# displayBoard.net
KiCad netlist of a schematic drawn in EAGLE
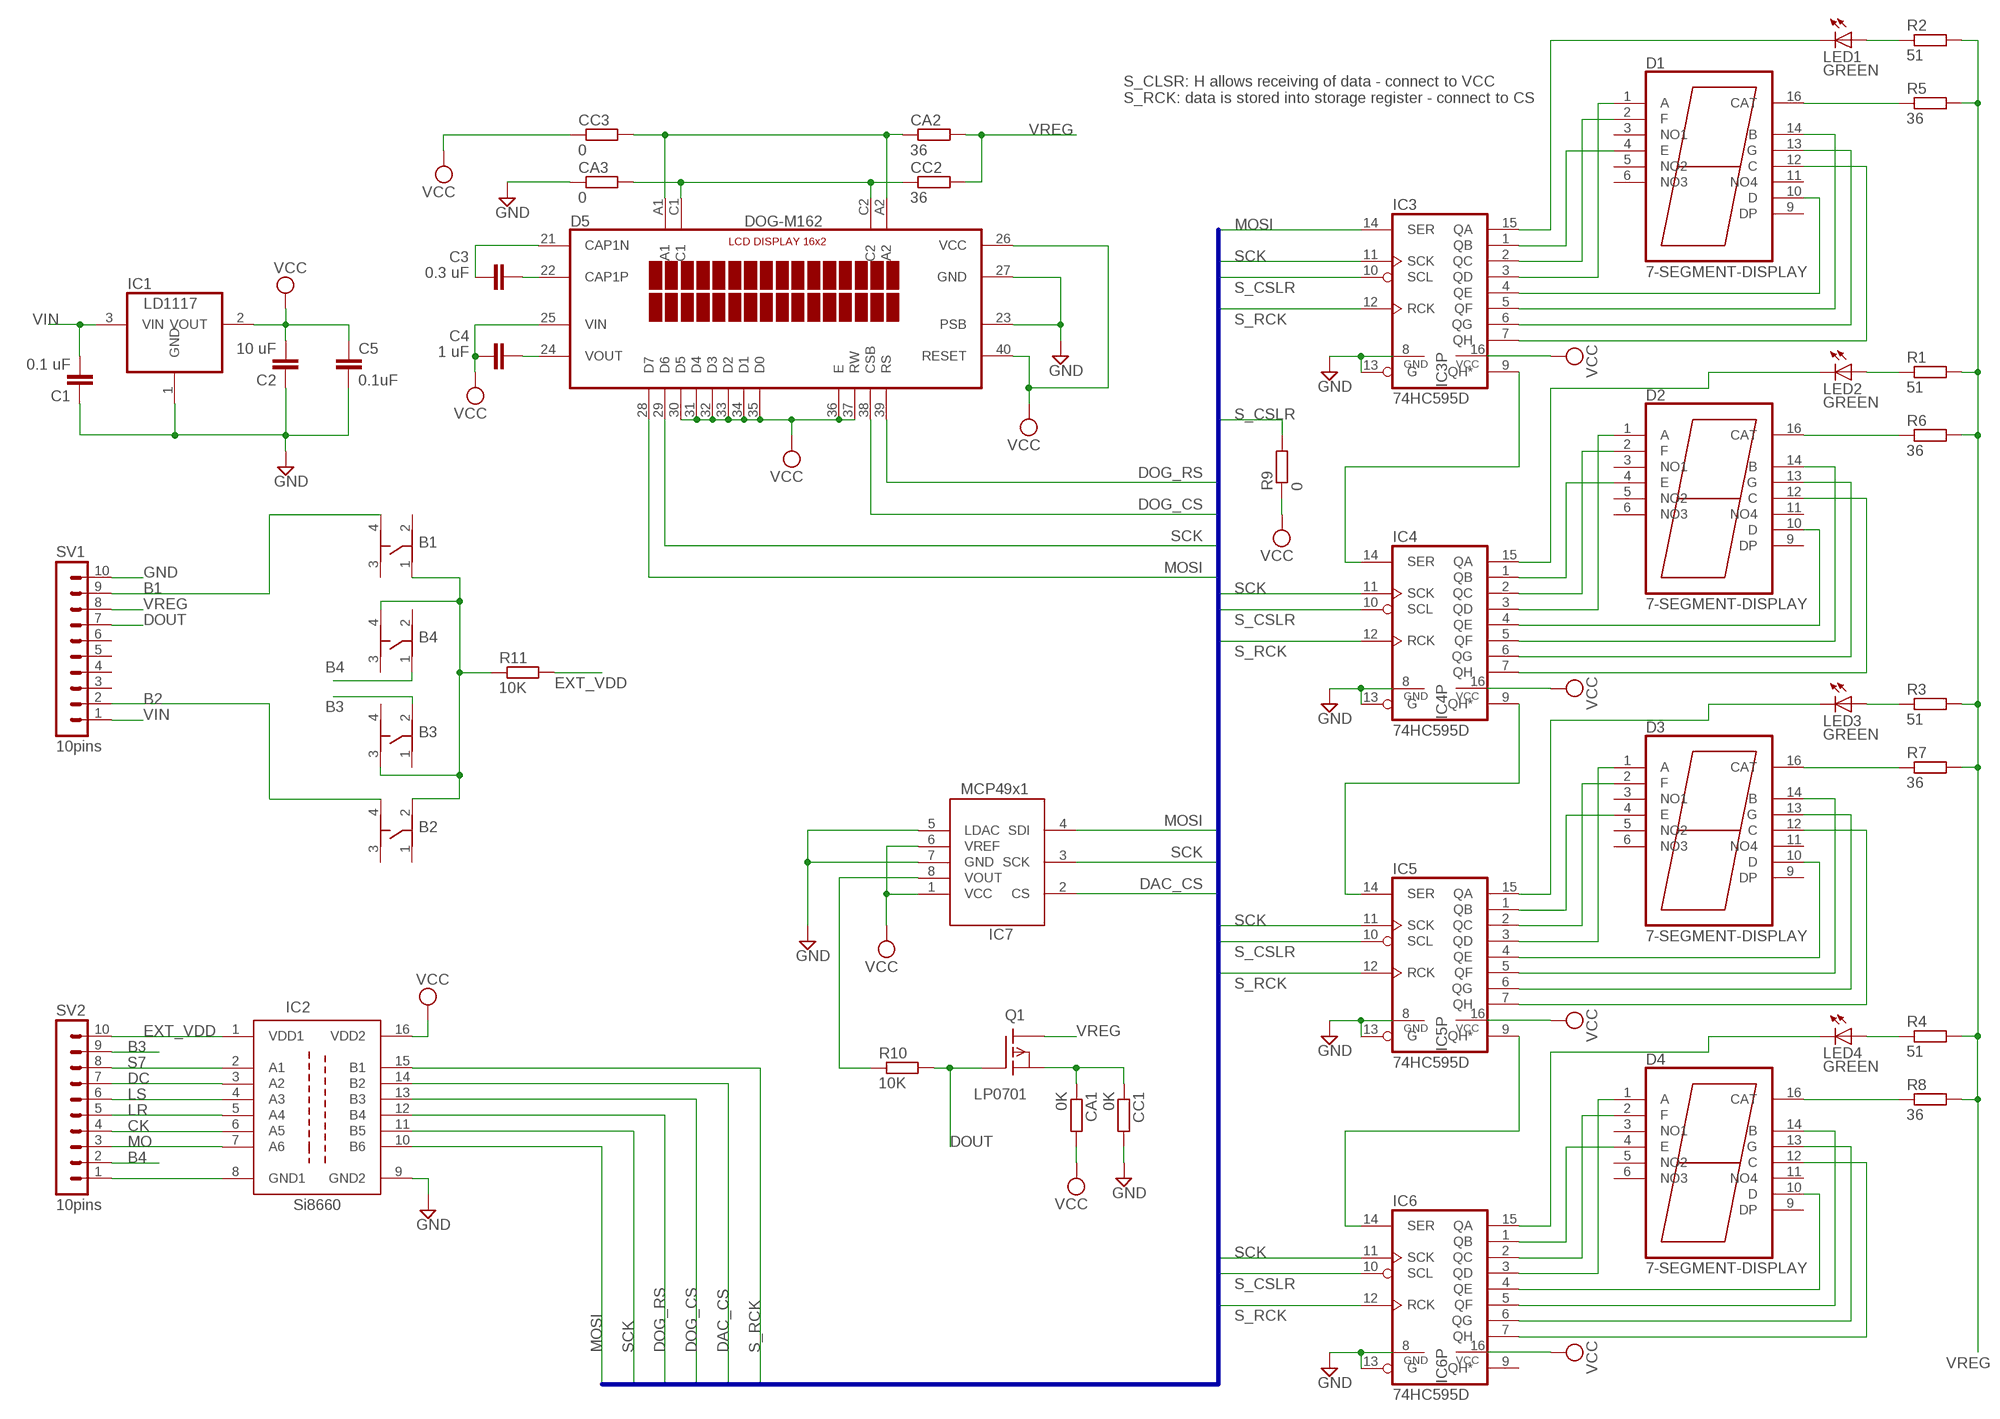
[diagram p0: schematic, sheet 1]

(export (version "E")
  (design (tool "Eeschema 10.0.6"))
  (components
    (comp (ref "B1")
      (value "BUTTON-D6X")
      (footprint "eagle-import:BUTTON-D6X")
      (libsource (lib "eagle-import") (part "BUTTON-D6X"))
    )
    (comp (ref "B2")
      (value "BUTTON-D6X")
      (footprint "eagle-import:BUTTON-D6X")
      (libsource (lib "eagle-import") (part "BUTTON-D6X"))
    )
    (comp (ref "B3")
      (value "BUTTON-D6X")
      (footprint "eagle-import:BUTTON-D6X")
      (libsource (lib "eagle-import") (part "BUTTON-D6X"))
    )
    (comp (ref "B4")
      (value "BUTTON-D6X")
      (footprint "eagle-import:BUTTON-D6X")
      (libsource (lib "eagle-import") (part "BUTTON-D6X"))
    )
    (comp (ref "C1")
      (value "0.1 uF")
      (footprint "eagle-import:C1206")
      (libsource (lib "eagle-import") (part "C-EUC1206"))
    )
    (comp (ref "C2")
      (value "10 uF")
      (footprint "eagle-import:C1206")
      (libsource (lib "eagle-import") (part "C-EUC1206"))
    )
    (comp (ref "C3")
      (value "0.3 uF")
      (footprint "eagle-import:C1206")
      (libsource (lib "eagle-import") (part "C-EUC1206"))
    )
    (comp (ref "C4")
      (value "1 uF")
      (footprint "eagle-import:C1206")
      (libsource (lib "eagle-import") (part "C-EUC1206"))
    )
    (comp (ref "C5")
      (value "0.1uF")
      (footprint "eagle-import:C1206")
      (libsource (lib "eagle-import") (part "C-EUC1206"))
    )
    (comp (ref "CA1")
      (value "0K")
      (footprint "eagle-import:R1206")
      (libsource (lib "eagle-import") (part "R-EU_R1206"))
    )
    (comp (ref "CA2")
      (value "36")
      (footprint "eagle-import:R1206")
      (libsource (lib "eagle-import") (part "R-EU_R1206"))
    )
    (comp (ref "CA3")
      (value "0")
      (footprint "eagle-import:R1206")
      (libsource (lib "eagle-import") (part "R-EU_R1206"))
    )
    (comp (ref "CC1")
      (value "0K")
      (footprint "eagle-import:R1206")
      (libsource (lib "eagle-import") (part "R-EU_R1206"))
    )
    (comp (ref "CC2")
      (value "36")
      (footprint "eagle-import:R1206")
      (libsource (lib "eagle-import") (part "R-EU_R1206"))
    )
    (comp (ref "CC3")
      (value "0")
      (footprint "eagle-import:R1206")
      (libsource (lib "eagle-import") (part "R-EU_R1206"))
    )
    (comp (ref "D1")
      (value "7-SEGMENT-DISPLAY")
      (footprint "eagle-import:LDS-A812")
      (libsource (lib "eagle-import") (part "7-SEGMENT-DISPLAY"))
    )
    (comp (ref "D2")
      (value "7-SEGMENT-DISPLAY")
      (footprint "eagle-import:LDS-A812")
      (libsource (lib "eagle-import") (part "7-SEGMENT-DISPLAY"))
    )
    (comp (ref "D3")
      (value "7-SEGMENT-DISPLAY")
      (footprint "eagle-import:LDS-A812")
      (libsource (lib "eagle-import") (part "7-SEGMENT-DISPLAY"))
    )
    (comp (ref "D4")
      (value "7-SEGMENT-DISPLAY")
      (footprint "eagle-import:LDS-A812")
      (libsource (lib "eagle-import") (part "7-SEGMENT-DISPLAY"))
    )
    (comp (ref "D5")
      (value "DOG-M162")
      (footprint "eagle-import:DOGM162")
      (libsource (lib "eagle-import") (part "DOG-M162"))
    )
    (comp (ref "IC1")
      (value "LD1117")
      (footprint "eagle-import:SOT223")
      (fields (field (name "MPN") "REG1117"))
      (libsource (lib "eagle-import") (part "REG1117"))
    )
    (comp (ref "IC2")
      (value "SI-8660")
      (footprint "eagle-import:SOP-16")
      (libsource (lib "eagle-import") (part "SI-8660"))
    )
    (comp (ref "IC3")
      (value "74HC595D")
      (footprint "eagle-import:SO16")
      (libsource (lib "eagle-import") (part "74595DHC"))
    )
    (comp (ref "IC4")
      (value "74HC595D")
      (footprint "eagle-import:SO16")
      (libsource (lib "eagle-import") (part "74595DHC"))
    )
    (comp (ref "IC5")
      (value "74HC595D")
      (footprint "eagle-import:SO16")
      (libsource (lib "eagle-import") (part "74595DHC"))
    )
    (comp (ref "IC6")
      (value "74HC595D")
      (footprint "eagle-import:SO16")
      (libsource (lib "eagle-import") (part "74595DHC"))
    )
    (comp (ref "IC7")
      (value "MCP4921")
      (footprint "eagle-import:MSOP-8")
      (libsource (lib "eagle-import") (part "MCP4901"))
    )
    (comp (ref "LED1")
      (value "GREEN")
      (footprint "eagle-import:LED3MM")
      (libsource (lib "eagle-import") (part "LED3MM"))
    )
    (comp (ref "LED2")
      (value "GREEN")
      (footprint "eagle-import:LED3MM")
      (libsource (lib "eagle-import") (part "LED3MM"))
    )
    (comp (ref "LED3")
      (value "GREEN")
      (footprint "eagle-import:LED3MM")
      (libsource (lib "eagle-import") (part "LED3MM"))
    )
    (comp (ref "LED4")
      (value "GREEN")
      (footprint "eagle-import:LED3MM")
      (libsource (lib "eagle-import") (part "LED3MM"))
    )
    (comp (ref "Q1")
      (value "LP0701")
      (footprint "eagle-import:TO-92")
      (libsource (lib "eagle-import") (part "LP0701N3"))
    )
    (comp (ref "R1")
      (value "51")
      (footprint "eagle-import:R1206")
      (libsource (lib "eagle-import") (part "R-EU_R1206"))
    )
    (comp (ref "R2")
      (value "51")
      (footprint "eagle-import:R1206")
      (libsource (lib "eagle-import") (part "R-EU_R1206"))
    )
    (comp (ref "R3")
      (value "51")
      (footprint "eagle-import:R1206")
      (libsource (lib "eagle-import") (part "R-EU_R1206"))
    )
    (comp (ref "R4")
      (value "51")
      (footprint "eagle-import:R1206")
      (libsource (lib "eagle-import") (part "R-EU_R1206"))
    )
    (comp (ref "R5")
      (value "36")
      (footprint "eagle-import:R1206")
      (libsource (lib "eagle-import") (part "R-EU_R1206"))
    )
    (comp (ref "R6")
      (value "36")
      (footprint "eagle-import:R1206")
      (libsource (lib "eagle-import") (part "R-EU_R1206"))
    )
    (comp (ref "R7")
      (value "36")
      (footprint "eagle-import:R1206")
      (libsource (lib "eagle-import") (part "R-EU_R1206"))
    )
    (comp (ref "R8")
      (value "36")
      (footprint "eagle-import:R1206")
      (libsource (lib "eagle-import") (part "R-EU_R1206"))
    )
    (comp (ref "R9")
      (value "0")
      (footprint "eagle-import:R1206")
      (libsource (lib "eagle-import") (part "R-EU_R1206"))
    )
    (comp (ref "R10")
      (value "10K")
      (footprint "eagle-import:R1206")
      (libsource (lib "eagle-import") (part "R-EU_R1206"))
    )
    (comp (ref "R11")
      (value "10K")
      (footprint "eagle-import:R1206")
      (libsource (lib "eagle-import") (part "R-EU_R1206"))
    )
    (comp (ref "SV1")
      (value "10pins")
      (footprint "eagle-import:MA10-1")
      (libsource (lib "eagle-import") (part "MA10-1"))
    )
    (comp (ref "SV2")
      (value "10pins")
      (footprint "eagle-import:MA10-1")
      (libsource (lib "eagle-import") (part "MA10-1"))
    )
  )
  (nets
    (net (code "1") (name "/B1") (class "Default")
      (node (ref "B1") (pin "4") (pinfunction "4_4") (pintype "bidirectional"))
      (node (ref "SV1") (pin "9") (pinfunction "9_9") (pintype "passive"))
    )
    (net (code "2") (name "/B2") (class "Default")
      (node (ref "B2") (pin "4") (pinfunction "4_4") (pintype "bidirectional"))
      (node (ref "SV1") (pin "2") (pinfunction "2_2") (pintype "passive"))
    )
    (net (code "3") (name "/B3") (class "Default")
      (node (ref "B3") (pin "2") (pinfunction "2_2") (pintype "bidirectional"))
      (node (ref "SV2") (pin "9") (pinfunction "9_9") (pintype "passive"))
    )
    (net (code "4") (name "/B4") (class "Default")
      (node (ref "B4") (pin "1") (pinfunction "1_1") (pintype "bidirectional"))
      (node (ref "SV2") (pin "2") (pinfunction "2_2") (pintype "passive"))
    )
    (net (code "5") (name "/CK") (class "Default")
      (node (ref "IC2") (pin "6") (pinfunction "A5_6") (pintype "bidirectional"))
      (node (ref "SV2") (pin "4") (pinfunction "4_4") (pintype "passive"))
    )
    (net (code "6") (name "/DAC_CS") (class "Default")
      (node (ref "IC2") (pin "14") (pinfunction "B2_14") (pintype "bidirectional"))
      (node (ref "IC7") (pin "2") (pinfunction "CS_2") (pintype "bidirectional"))
    )
    (net (code "7") (name "/DC") (class "Default")
      (node (ref "IC2") (pin "3") (pinfunction "A2_3") (pintype "bidirectional"))
      (node (ref "SV2") (pin "7") (pinfunction "7_7") (pintype "passive"))
    )
    (net (code "8") (name "/DOG_CS") (class "Default")
      (node (ref "D5") (pin "38") (pinfunction "CSB_38") (pintype "bidirectional"))
      (node (ref "IC2") (pin "13") (pinfunction "B3_13") (pintype "bidirectional"))
    )
    (net (code "9") (name "/DOG_RS") (class "Default")
      (node (ref "D5") (pin "39") (pinfunction "RS_39") (pintype "bidirectional"))
      (node (ref "IC2") (pin "12") (pinfunction "B4_12") (pintype "bidirectional"))
    )
    (net (code "10") (name "/DOUT") (class "Default")
      (node (ref "Q1") (pin "2") (pinfunction "G_2") (pintype "passive"))
      (node (ref "R10") (pin "2") (pinfunction "2_2") (pintype "passive"))
      (node (ref "SV1") (pin "7") (pinfunction "7_7") (pintype "passive"))
    )
    (net (code "11") (name "/EXT_VDD") (class "Default")
      (node (ref "IC2") (pin "1") (pinfunction "VDD1_1") (pintype "bidirectional"))
      (node (ref "R11") (pin "2") (pinfunction "2_2") (pintype "passive"))
      (node (ref "SV2") (pin "10") (pinfunction "10_10") (pintype "passive"))
    )
    (net (code "12") (name "/LR") (class "Default")
      (node (ref "IC2") (pin "5") (pinfunction "A4_5") (pintype "bidirectional"))
      (node (ref "SV2") (pin "5") (pinfunction "5_5") (pintype "passive"))
    )
    (net (code "13") (name "/LS") (class "Default")
      (node (ref "IC2") (pin "4") (pinfunction "A3_4") (pintype "bidirectional"))
      (node (ref "SV2") (pin "6") (pinfunction "6_6") (pintype "passive"))
    )
    (net (code "14") (name "/MO") (class "Default")
      (node (ref "IC2") (pin "7") (pinfunction "A6_7") (pintype "bidirectional"))
      (node (ref "SV2") (pin "3") (pinfunction "3_3") (pintype "passive"))
    )
    (net (code "15") (name "/MOSI") (class "Default")
      (node (ref "D5") (pin "28") (pinfunction "D7_28") (pintype "bidirectional"))
      (node (ref "IC2") (pin "10") (pinfunction "B6_10") (pintype "bidirectional"))
      (node (ref "IC3") (pin "14") (pinfunction "SER_14") (pintype "input"))
      (node (ref "IC7") (pin "4") (pinfunction "SDI_4") (pintype "bidirectional"))
    )
    (net (code "16") (name "/S7") (class "Default")
      (node (ref "IC2") (pin "2") (pinfunction "A1_2") (pintype "bidirectional"))
      (node (ref "SV2") (pin "8") (pinfunction "8_8") (pintype "passive"))
    )
    (net (code "17") (name "/SCK") (class "Default")
      (node (ref "D5") (pin "29") (pinfunction "D6_29") (pintype "bidirectional"))
      (node (ref "IC2") (pin "11") (pinfunction "B5_11") (pintype "bidirectional"))
      (node (ref "IC3") (pin "11") (pinfunction "SCK_11") (pintype "input"))
      (node (ref "IC4") (pin "11") (pinfunction "SCK_11") (pintype "input"))
      (node (ref "IC5") (pin "11") (pinfunction "SCK_11") (pintype "input"))
      (node (ref "IC6") (pin "11") (pinfunction "SCK_11") (pintype "input"))
      (node (ref "IC7") (pin "3") (pinfunction "SCK_3") (pintype "bidirectional"))
    )
    (net (code "18") (name "/S_CSLR") (class "Default")
      (node (ref "IC3") (pin "10") (pinfunction "SCL_10") (pintype "input"))
      (node (ref "IC4") (pin "10") (pinfunction "SCL_10") (pintype "input"))
      (node (ref "IC5") (pin "10") (pinfunction "SCL_10") (pintype "input"))
      (node (ref "IC6") (pin "10") (pinfunction "SCL_10") (pintype "input"))
      (node (ref "R9") (pin "2") (pinfunction "2_2") (pintype "passive"))
    )
    (net (code "19") (name "/S_RCK") (class "Default")
      (node (ref "IC2") (pin "15") (pinfunction "B1_15") (pintype "bidirectional"))
      (node (ref "IC3") (pin "12") (pinfunction "RCK_12") (pintype "input"))
      (node (ref "IC4") (pin "12") (pinfunction "RCK_12") (pintype "input"))
      (node (ref "IC5") (pin "12") (pinfunction "RCK_12") (pintype "input"))
      (node (ref "IC6") (pin "12") (pinfunction "RCK_12") (pintype "input"))
    )
    (net (code "20") (name "/VIN") (class "Default")
      (node (ref "C1") (pin "2") (pinfunction "2_2") (pintype "passive"))
      (node (ref "IC1") (pin "3") (pinfunction "VIN_3") (pintype "input"))
      (node (ref "SV1") (pin "1") (pinfunction "1_1") (pintype "passive"))
    )
    (net (code "21") (name "/VREG") (class "Default")
      (node (ref "CA2") (pin "2") (pinfunction "2_2") (pintype "passive"))
      (node (ref "CC2") (pin "2") (pinfunction "2_2") (pintype "passive"))
      (node (ref "Q1") (pin "3") (pinfunction "D_3") (pintype "passive"))
      (node (ref "R1") (pin "2") (pinfunction "2_2") (pintype "passive"))
      (node (ref "R2") (pin "2") (pinfunction "2_2") (pintype "passive"))
      (node (ref "R3") (pin "2") (pinfunction "2_2") (pintype "passive"))
      (node (ref "R4") (pin "2") (pinfunction "2_2") (pintype "passive"))
      (node (ref "R5") (pin "2") (pinfunction "2_2") (pintype "passive"))
      (node (ref "R6") (pin "2") (pinfunction "2_2") (pintype "passive"))
      (node (ref "R7") (pin "2") (pinfunction "2_2") (pintype "passive"))
      (node (ref "R8") (pin "2") (pinfunction "2_2") (pintype "passive"))
      (node (ref "SV1") (pin "8") (pinfunction "8_8") (pintype "passive"))
    )
    (net (code "22") (name "GND") (class "Default")
      (node (ref "C1") (pin "1") (pinfunction "1_1") (pintype "passive"))
      (node (ref "C2") (pin "1") (pinfunction "1_1") (pintype "passive"))
      (node (ref "C5") (pin "2") (pinfunction "2_2") (pintype "passive"))
      (node (ref "CA3") (pin "1") (pinfunction "1_1") (pintype "passive"))
      (node (ref "CC1") (pin "2") (pinfunction "2_2") (pintype "passive"))
      (node (ref "D5") (pin "23") (pinfunction "PSB_23") (pintype "bidirectional"))
      (node (ref "D5") (pin "27") (pinfunction "GND_27") (pintype "power_in"))
      (node (ref "IC1") (pin "1") (pinfunction "GND_1") (pintype "power_in"))
      (node (ref "IC2") (pin "9") (pinfunction "GND2_9") (pintype "bidirectional"))
      (node (ref "IC3") (pin "13") (pinfunction "G_13") (pintype "input"))
      (node (ref "IC3") (pin "8") (pinfunction "GND_8") (pintype "power_in"))
      (node (ref "IC4") (pin "13") (pinfunction "G_13") (pintype "input"))
      (node (ref "IC4") (pin "8") (pinfunction "GND_8") (pintype "power_in"))
      (node (ref "IC5") (pin "13") (pinfunction "G_13") (pintype "input"))
      (node (ref "IC5") (pin "8") (pinfunction "GND_8") (pintype "power_in"))
      (node (ref "IC6") (pin "13") (pinfunction "G_13") (pintype "input"))
      (node (ref "IC6") (pin "8") (pinfunction "GND_8") (pintype "power_in"))
      (node (ref "IC7") (pin "5") (pinfunction "LDAC_5") (pintype "bidirectional"))
      (node (ref "IC7") (pin "7") (pinfunction "GND_7") (pintype "power_in"))
      (node (ref "SV1") (pin "10") (pinfunction "10_10") (pintype "passive"))
    )
    (net (code "23") (name "Net-(B1-Pad1)") (class "Default")
      (node (ref "B1") (pin "1") (pinfunction "1_1") (pintype "bidirectional"))
      (node (ref "B2") (pin "2") (pinfunction "2_2") (pintype "bidirectional"))
      (node (ref "B3") (pin "3") (pinfunction "3_3") (pintype "bidirectional"))
      (node (ref "B4") (pin "4") (pinfunction "4_4") (pintype "bidirectional"))
      (node (ref "R11") (pin "1") (pinfunction "1_1") (pintype "passive"))
    )
    (net (code "24") (name "Net-(CA2-Pad1)") (class "Default")
      (node (ref "CA2") (pin "1") (pinfunction "1_1") (pintype "passive"))
      (node (ref "CC3") (pin "2") (pinfunction "2_2") (pintype "passive"))
      (node (ref "D5") (pin "A1") (pinfunction "A1_A1") (pintype "bidirectional"))
      (node (ref "D5") (pin "A2") (pinfunction "A2_A2") (pintype "bidirectional"))
    )
    (net (code "25") (name "Net-(CA3-Pad2)") (class "Default")
      (node (ref "CA3") (pin "2") (pinfunction "2_2") (pintype "passive"))
      (node (ref "CC2") (pin "1") (pinfunction "1_1") (pintype "passive"))
      (node (ref "D5") (pin "C1") (pinfunction "C1_C1") (pintype "bidirectional"))
      (node (ref "D5") (pin "C2") (pinfunction "C2_C2") (pintype "bidirectional"))
    )
    (net (code "26") (name "Net-(D1-A)") (class "Default")
      (node (ref "D1") (pin "1") (pinfunction "A_1") (pintype "input"))
      (node (ref "IC3") (pin "3") (pinfunction "QD_3") (pintype "tri_state"))
    )
    (net (code "27") (name "Net-(D1-B)") (class "Default")
      (node (ref "D1") (pin "14") (pinfunction "B_14") (pintype "input"))
      (node (ref "IC3") (pin "5") (pinfunction "QF_5") (pintype "tri_state"))
    )
    (net (code "28") (name "Net-(D1-C)") (class "Default")
      (node (ref "D1") (pin "12") (pinfunction "C_12") (pintype "input"))
      (node (ref "IC3") (pin "7") (pinfunction "QH_7") (pintype "tri_state"))
    )
    (net (code "29") (name "Net-(D1-CAT)") (class "Default")
      (node (ref "D1") (pin "16") (pinfunction "CAT_16") (pintype "bidirectional"))
      (node (ref "R5") (pin "1") (pinfunction "1_1") (pintype "passive"))
    )
    (net (code "30") (name "Net-(D1-D)") (class "Default")
      (node (ref "D1") (pin "10") (pinfunction "D_10") (pintype "input"))
      (node (ref "IC3") (pin "4") (pinfunction "QE_4") (pintype "tri_state"))
    )
    (net (code "31") (name "Net-(D1-E)") (class "Default")
      (node (ref "D1") (pin "4") (pinfunction "E_4") (pintype "input"))
      (node (ref "IC3") (pin "1") (pinfunction "QB_1") (pintype "tri_state"))
    )
    (net (code "32") (name "Net-(D1-F)") (class "Default")
      (node (ref "D1") (pin "2") (pinfunction "F_2") (pintype "input"))
      (node (ref "IC3") (pin "2") (pinfunction "QC_2") (pintype "tri_state"))
    )
    (net (code "33") (name "Net-(D1-G)") (class "Default")
      (node (ref "D1") (pin "13") (pinfunction "G_13") (pintype "input"))
      (node (ref "IC3") (pin "6") (pinfunction "QG_6") (pintype "tri_state"))
    )
    (net (code "34") (name "Net-(D2-A)") (class "Default")
      (node (ref "D2") (pin "1") (pinfunction "A_1") (pintype "input"))
      (node (ref "IC4") (pin "3") (pinfunction "QD_3") (pintype "tri_state"))
    )
    (net (code "35") (name "Net-(D2-B)") (class "Default")
      (node (ref "D2") (pin "14") (pinfunction "B_14") (pintype "input"))
      (node (ref "IC4") (pin "5") (pinfunction "QF_5") (pintype "tri_state"))
    )
    (net (code "36") (name "Net-(D2-C)") (class "Default")
      (node (ref "D2") (pin "12") (pinfunction "C_12") (pintype "input"))
      (node (ref "IC4") (pin "7") (pinfunction "QH_7") (pintype "tri_state"))
    )
    (net (code "37") (name "Net-(D2-CAT)") (class "Default")
      (node (ref "D2") (pin "16") (pinfunction "CAT_16") (pintype "bidirectional"))
      (node (ref "R6") (pin "1") (pinfunction "1_1") (pintype "passive"))
    )
    (net (code "38") (name "Net-(D2-D)") (class "Default")
      (node (ref "D2") (pin "10") (pinfunction "D_10") (pintype "input"))
      (node (ref "IC4") (pin "4") (pinfunction "QE_4") (pintype "tri_state"))
    )
    (net (code "39") (name "Net-(D2-E)") (class "Default")
      (node (ref "D2") (pin "4") (pinfunction "E_4") (pintype "input"))
      (node (ref "IC4") (pin "1") (pinfunction "QB_1") (pintype "tri_state"))
    )
    (net (code "40") (name "Net-(D2-F)") (class "Default")
      (node (ref "D2") (pin "2") (pinfunction "F_2") (pintype "input"))
      (node (ref "IC4") (pin "2") (pinfunction "QC_2") (pintype "tri_state"))
    )
    (net (code "41") (name "Net-(D2-G)") (class "Default")
      (node (ref "D2") (pin "13") (pinfunction "G_13") (pintype "input"))
      (node (ref "IC4") (pin "6") (pinfunction "QG_6") (pintype "tri_state"))
    )
    (net (code "42") (name "Net-(D3-A)") (class "Default")
      (node (ref "D3") (pin "1") (pinfunction "A_1") (pintype "input"))
      (node (ref "IC5") (pin "3") (pinfunction "QD_3") (pintype "tri_state"))
    )
    (net (code "43") (name "Net-(D3-B)") (class "Default")
      (node (ref "D3") (pin "14") (pinfunction "B_14") (pintype "input"))
      (node (ref "IC5") (pin "5") (pinfunction "QF_5") (pintype "tri_state"))
    )
    (net (code "44") (name "Net-(D3-C)") (class "Default")
      (node (ref "D3") (pin "12") (pinfunction "C_12") (pintype "input"))
      (node (ref "IC5") (pin "7") (pinfunction "QH_7") (pintype "tri_state"))
    )
    (net (code "45") (name "Net-(D3-CAT)") (class "Default")
      (node (ref "D3") (pin "16") (pinfunction "CAT_16") (pintype "bidirectional"))
      (node (ref "R7") (pin "1") (pinfunction "1_1") (pintype "passive"))
    )
    (net (code "46") (name "Net-(D3-D)") (class "Default")
      (node (ref "D3") (pin "10") (pinfunction "D_10") (pintype "input"))
      (node (ref "IC5") (pin "4") (pinfunction "QE_4") (pintype "tri_state"))
    )
    (net (code "47") (name "Net-(D3-E)") (class "Default")
      (node (ref "D3") (pin "4") (pinfunction "E_4") (pintype "input"))
      (node (ref "IC5") (pin "1") (pinfunction "QB_1") (pintype "tri_state"))
    )
    (net (code "48") (name "Net-(D3-F)") (class "Default")
      (node (ref "D3") (pin "2") (pinfunction "F_2") (pintype "input"))
      (node (ref "IC5") (pin "2") (pinfunction "QC_2") (pintype "tri_state"))
    )
    (net (code "49") (name "Net-(D3-G)") (class "Default")
      (node (ref "D3") (pin "13") (pinfunction "G_13") (pintype "input"))
      (node (ref "IC5") (pin "6") (pinfunction "QG_6") (pintype "tri_state"))
    )
    (net (code "50") (name "Net-(D4-A)") (class "Default")
      (node (ref "D4") (pin "1") (pinfunction "A_1") (pintype "input"))
      (node (ref "IC6") (pin "3") (pinfunction "QD_3") (pintype "tri_state"))
    )
    (net (code "51") (name "Net-(D4-B)") (class "Default")
      (node (ref "D4") (pin "14") (pinfunction "B_14") (pintype "input"))
      (node (ref "IC6") (pin "5") (pinfunction "QF_5") (pintype "tri_state"))
    )
    (net (code "52") (name "Net-(D4-C)") (class "Default")
      (node (ref "D4") (pin "12") (pinfunction "C_12") (pintype "input"))
      (node (ref "IC6") (pin "7") (pinfunction "QH_7") (pintype "tri_state"))
    )
    (net (code "53") (name "Net-(D4-CAT)") (class "Default")
      (node (ref "D4") (pin "16") (pinfunction "CAT_16") (pintype "bidirectional"))
      (node (ref "R8") (pin "1") (pinfunction "1_1") (pintype "passive"))
    )
    (net (code "54") (name "Net-(D4-D)") (class "Default")
      (node (ref "D4") (pin "10") (pinfunction "D_10") (pintype "input"))
      (node (ref "IC6") (pin "4") (pinfunction "QE_4") (pintype "tri_state"))
    )
    (net (code "55") (name "Net-(D4-E)") (class "Default")
      (node (ref "D4") (pin "4") (pinfunction "E_4") (pintype "input"))
      (node (ref "IC6") (pin "1") (pinfunction "QB_1") (pintype "tri_state"))
    )
    (net (code "56") (name "Net-(D4-F)") (class "Default")
      (node (ref "D4") (pin "2") (pinfunction "F_2") (pintype "input"))
      (node (ref "IC6") (pin "2") (pinfunction "QC_2") (pintype "tri_state"))
    )
    (net (code "57") (name "Net-(D4-G)") (class "Default")
      (node (ref "D4") (pin "13") (pinfunction "G_13") (pintype "input"))
      (node (ref "IC6") (pin "6") (pinfunction "QG_6") (pintype "tri_state"))
    )
    (net (code "58") (name "Net-(D5-CAP1N)") (class "Default")
      (node (ref "C3") (pin "1") (pinfunction "1_1") (pintype "passive"))
      (node (ref "D5") (pin "21") (pinfunction "CAP1N_21") (pintype "bidirectional"))
    )
    (net (code "59") (name "Net-(D5-CAP1P)") (class "Default")
      (node (ref "C3") (pin "2") (pinfunction "2_2") (pintype "passive"))
      (node (ref "D5") (pin "22") (pinfunction "CAP1P_22") (pintype "bidirectional"))
    )
    (net (code "60") (name "Net-(D5-VOUT)") (class "Default")
      (node (ref "C4") (pin "1") (pinfunction "1_1") (pintype "passive"))
      (node (ref "D5") (pin "24") (pinfunction "VOUT_24") (pintype "bidirectional"))
    )
    (net (code "61") (name "Net-(IC2-GND1)") (class "Default")
      (node (ref "IC2") (pin "8") (pinfunction "GND1_8") (pintype "bidirectional"))
      (node (ref "SV2") (pin "1") (pinfunction "1_1") (pintype "passive"))
    )
    (net (code "62") (name "Net-(IC3A-QA)") (class "Default")
      (node (ref "IC3") (pin "15") (pinfunction "QA_15") (pintype "tri_state"))
      (node (ref "LED1") (pin "K") (pinfunction "C_K") (pintype "passive"))
    )
    (net (code "63") (name "Net-(IC3A-QH*)") (class "Default")
      (node (ref "IC3") (pin "9") (pinfunction "QH*_9") (pintype "tri_state"))
      (node (ref "IC4") (pin "14") (pinfunction "SER_14") (pintype "input"))
    )
    (net (code "64") (name "Net-(IC4A-QA)") (class "Default")
      (node (ref "IC4") (pin "15") (pinfunction "QA_15") (pintype "tri_state"))
      (node (ref "LED2") (pin "K") (pinfunction "C_K") (pintype "passive"))
    )
    (net (code "65") (name "Net-(IC4A-QH*)") (class "Default")
      (node (ref "IC4") (pin "9") (pinfunction "QH*_9") (pintype "tri_state"))
      (node (ref "IC5") (pin "14") (pinfunction "SER_14") (pintype "input"))
    )
    (net (code "66") (name "Net-(IC5A-QA)") (class "Default")
      (node (ref "IC5") (pin "15") (pinfunction "QA_15") (pintype "tri_state"))
      (node (ref "LED3") (pin "K") (pinfunction "C_K") (pintype "passive"))
    )
    (net (code "67") (name "Net-(IC5A-QH*)") (class "Default")
      (node (ref "IC5") (pin "9") (pinfunction "QH*_9") (pintype "tri_state"))
      (node (ref "IC6") (pin "14") (pinfunction "SER_14") (pintype "input"))
    )
    (net (code "68") (name "Net-(IC6A-QA)") (class "Default")
      (node (ref "IC6") (pin "15") (pinfunction "QA_15") (pintype "tri_state"))
      (node (ref "LED4") (pin "K") (pinfunction "C_K") (pintype "passive"))
    )
    (net (code "69") (name "Net-(IC7-VOUT)") (class "Default")
      (node (ref "IC7") (pin "8") (pinfunction "VOUT_8") (pintype "bidirectional"))
      (node (ref "R10") (pin "1") (pinfunction "1_1") (pintype "passive"))
    )
    (net (code "70") (name "Net-(LED1-PadA)") (class "Default")
      (node (ref "LED1") (pin "A") (pinfunction "A_A") (pintype "passive"))
      (node (ref "R2") (pin "1") (pinfunction "1_1") (pintype "passive"))
    )
    (net (code "71") (name "Net-(LED2-PadA)") (class "Default")
      (node (ref "LED2") (pin "A") (pinfunction "A_A") (pintype "passive"))
      (node (ref "R1") (pin "1") (pinfunction "1_1") (pintype "passive"))
    )
    (net (code "72") (name "Net-(LED3-PadA)") (class "Default")
      (node (ref "LED3") (pin "A") (pinfunction "A_A") (pintype "passive"))
      (node (ref "R3") (pin "1") (pinfunction "1_1") (pintype "passive"))
    )
    (net (code "73") (name "Net-(LED4-PadA)") (class "Default")
      (node (ref "LED4") (pin "A") (pinfunction "A_A") (pintype "passive"))
      (node (ref "R4") (pin "1") (pinfunction "1_1") (pintype "passive"))
    )
    (net (code "74") (name "Net-(Q1-S)") (class "Default")
      (node (ref "CA1") (pin "1") (pinfunction "1_1") (pintype "passive"))
      (node (ref "CC1") (pin "1") (pinfunction "1_1") (pintype "passive"))
      (node (ref "Q1") (pin "1") (pinfunction "S_1") (pintype "passive"))
    )
    (net (code "75") (name "VCC") (class "Default")
      (node (ref "C2") (pin "2") (pinfunction "2_2") (pintype "passive"))
      (node (ref "C4") (pin "2") (pinfunction "2_2") (pintype "passive"))
      (node (ref "C5") (pin "1") (pinfunction "1_1") (pintype "passive"))
      (node (ref "CA1") (pin "2") (pinfunction "2_2") (pintype "passive"))
      (node (ref "CC3") (pin "1") (pinfunction "1_1") (pintype "passive"))
      (node (ref "D5") (pin "25") (pinfunction "VIN_25") (pintype "bidirectional"))
      (node (ref "D5") (pin "26") (pinfunction "VCC_26") (pintype "power_in"))
      (node (ref "D5") (pin "30") (pinfunction "D5_30") (pintype "bidirectional"))
      (node (ref "D5") (pin "31") (pinfunction "D4_31") (pintype "bidirectional"))
      (node (ref "D5") (pin "32") (pinfunction "D3_32") (pintype "bidirectional"))
      (node (ref "D5") (pin "33") (pinfunction "D2_33") (pintype "bidirectional"))
      (node (ref "D5") (pin "34") (pinfunction "D1_34") (pintype "bidirectional"))
      (node (ref "D5") (pin "35") (pinfunction "D0_35") (pintype "bidirectional"))
      (node (ref "D5") (pin "36") (pinfunction "E_36") (pintype "bidirectional"))
      (node (ref "D5") (pin "37") (pinfunction "RW_37") (pintype "bidirectional"))
      (node (ref "D5") (pin "40") (pinfunction "RESET_40") (pintype "bidirectional"))
      (node (ref "IC1") (pin "2") (pinfunction "VOUT_2") (pintype "power_in"))
      (node (ref "IC2") (pin "16") (pinfunction "VDD2_16") (pintype "bidirectional"))
      (node (ref "IC3") (pin "16") (pinfunction "VCC_16") (pintype "power_in"))
      (node (ref "IC4") (pin "16") (pinfunction "VCC_16") (pintype "power_in"))
      (node (ref "IC5") (pin "16") (pinfunction "VCC_16") (pintype "power_in"))
      (node (ref "IC6") (pin "16") (pinfunction "VCC_16") (pintype "power_in"))
      (node (ref "IC7") (pin "1") (pinfunction "VCC_1") (pintype "power_in"))
      (node (ref "IC7") (pin "6") (pinfunction "VREF_6") (pintype "bidirectional"))
      (node (ref "R9") (pin "1") (pinfunction "1_1") (pintype "passive"))
    )
    (net (code "76") (name "unconnected-(B1-Pad2)") (class "Default")
      (node (ref "B1") (pin "2") (pinfunction "2_2") (pintype "bidirectional"))
    )
    (net (code "77") (name "unconnected-(B1-Pad3)") (class "Default")
      (node (ref "B1") (pin "3") (pinfunction "3_3") (pintype "bidirectional"))
    )
    (net (code "78") (name "unconnected-(B2-Pad1)") (class "Default")
      (node (ref "B2") (pin "1") (pinfunction "1_1") (pintype "bidirectional"))
    )
    (net (code "79") (name "unconnected-(B2-Pad3)") (class "Default")
      (node (ref "B2") (pin "3") (pinfunction "3_3") (pintype "bidirectional"))
    )
    (net (code "80") (name "unconnected-(B3-Pad1)") (class "Default")
      (node (ref "B3") (pin "1") (pinfunction "1_1") (pintype "bidirectional"))
    )
    (net (code "81") (name "unconnected-(B3-Pad4)") (class "Default")
      (node (ref "B3") (pin "4") (pinfunction "4_4") (pintype "bidirectional"))
    )
    (net (code "82") (name "unconnected-(B4-Pad2)") (class "Default")
      (node (ref "B4") (pin "2") (pinfunction "2_2") (pintype "bidirectional"))
    )
    (net (code "83") (name "unconnected-(B4-Pad3)") (class "Default")
      (node (ref "B4") (pin "3") (pinfunction "3_3") (pintype "bidirectional"))
    )
    (net (code "84") (name "unconnected-(D1-DP-Pad9)") (class "Default")
      (node (ref "D1") (pin "9") (pinfunction "DP_9") (pintype "bidirectional"))
    )
    (net (code "85") (name "unconnected-(D1-NO1-Pad3)") (class "Default")
      (node (ref "D1") (pin "3") (pinfunction "NO1_3") (pintype "bidirectional"))
    )
    (net (code "86") (name "unconnected-(D1-NO2-Pad5)") (class "Default")
      (node (ref "D1") (pin "5") (pinfunction "NO2_5") (pintype "bidirectional"))
    )
    (net (code "87") (name "unconnected-(D1-NO3-Pad6)") (class "Default")
      (node (ref "D1") (pin "6") (pinfunction "NO3_6") (pintype "bidirectional"))
    )
    (net (code "88") (name "unconnected-(D1-NO4-Pad11)") (class "Default")
      (node (ref "D1") (pin "11") (pinfunction "NO4_11") (pintype "bidirectional"))
    )
    (net (code "89") (name "unconnected-(D2-DP-Pad9)") (class "Default")
      (node (ref "D2") (pin "9") (pinfunction "DP_9") (pintype "bidirectional"))
    )
    (net (code "90") (name "unconnected-(D2-NO1-Pad3)") (class "Default")
      (node (ref "D2") (pin "3") (pinfunction "NO1_3") (pintype "bidirectional"))
    )
    (net (code "91") (name "unconnected-(D2-NO2-Pad5)") (class "Default")
      (node (ref "D2") (pin "5") (pinfunction "NO2_5") (pintype "bidirectional"))
    )
    (net (code "92") (name "unconnected-(D2-NO3-Pad6)") (class "Default")
      (node (ref "D2") (pin "6") (pinfunction "NO3_6") (pintype "bidirectional"))
    )
    (net (code "93") (name "unconnected-(D2-NO4-Pad11)") (class "Default")
      (node (ref "D2") (pin "11") (pinfunction "NO4_11") (pintype "bidirectional"))
    )
    (net (code "94") (name "unconnected-(D3-DP-Pad9)") (class "Default")
      (node (ref "D3") (pin "9") (pinfunction "DP_9") (pintype "bidirectional"))
    )
    (net (code "95") (name "unconnected-(D3-NO1-Pad3)") (class "Default")
      (node (ref "D3") (pin "3") (pinfunction "NO1_3") (pintype "bidirectional"))
    )
    (net (code "96") (name "unconnected-(D3-NO2-Pad5)") (class "Default")
      (node (ref "D3") (pin "5") (pinfunction "NO2_5") (pintype "bidirectional"))
    )
    (net (code "97") (name "unconnected-(D3-NO3-Pad6)") (class "Default")
      (node (ref "D3") (pin "6") (pinfunction "NO3_6") (pintype "bidirectional"))
    )
    (net (code "98") (name "unconnected-(D3-NO4-Pad11)") (class "Default")
      (node (ref "D3") (pin "11") (pinfunction "NO4_11") (pintype "bidirectional"))
    )
    (net (code "99") (name "unconnected-(D4-DP-Pad9)") (class "Default")
      (node (ref "D4") (pin "9") (pinfunction "DP_9") (pintype "bidirectional"))
    )
    (net (code "100") (name "unconnected-(D4-NO1-Pad3)") (class "Default")
      (node (ref "D4") (pin "3") (pinfunction "NO1_3") (pintype "bidirectional"))
    )
    (net (code "101") (name "unconnected-(D4-NO2-Pad5)") (class "Default")
      (node (ref "D4") (pin "5") (pinfunction "NO2_5") (pintype "bidirectional"))
    )
    (net (code "102") (name "unconnected-(D4-NO3-Pad6)") (class "Default")
      (node (ref "D4") (pin "6") (pinfunction "NO3_6") (pintype "bidirectional"))
    )
    (net (code "103") (name "unconnected-(D4-NO4-Pad11)") (class "Default")
      (node (ref "D4") (pin "11") (pinfunction "NO4_11") (pintype "bidirectional"))
    )
    (net (code "104") (name "unconnected-(IC6A-QH*-Pad9)") (class "Default")
      (node (ref "IC6") (pin "9") (pinfunction "QH*_9") (pintype "tri_state"))
    )
    (net (code "105") (name "unconnected-(SV1-Pad3)") (class "Default")
      (node (ref "SV1") (pin "3") (pinfunction "3_3") (pintype "passive"))
    )
    (net (code "106") (name "unconnected-(SV1-Pad4)") (class "Default")
      (node (ref "SV1") (pin "4") (pinfunction "4_4") (pintype "passive"))
    )
    (net (code "107") (name "unconnected-(SV1-Pad5)") (class "Default")
      (node (ref "SV1") (pin "5") (pinfunction "5_5") (pintype "passive"))
    )
    (net (code "108") (name "unconnected-(SV1-Pad6)") (class "Default")
      (node (ref "SV1") (pin "6") (pinfunction "6_6") (pintype "passive"))
    )
  )
)
